# stm32f4x7v.net
KiCad netlist of a schematic drawn in Altium Designer
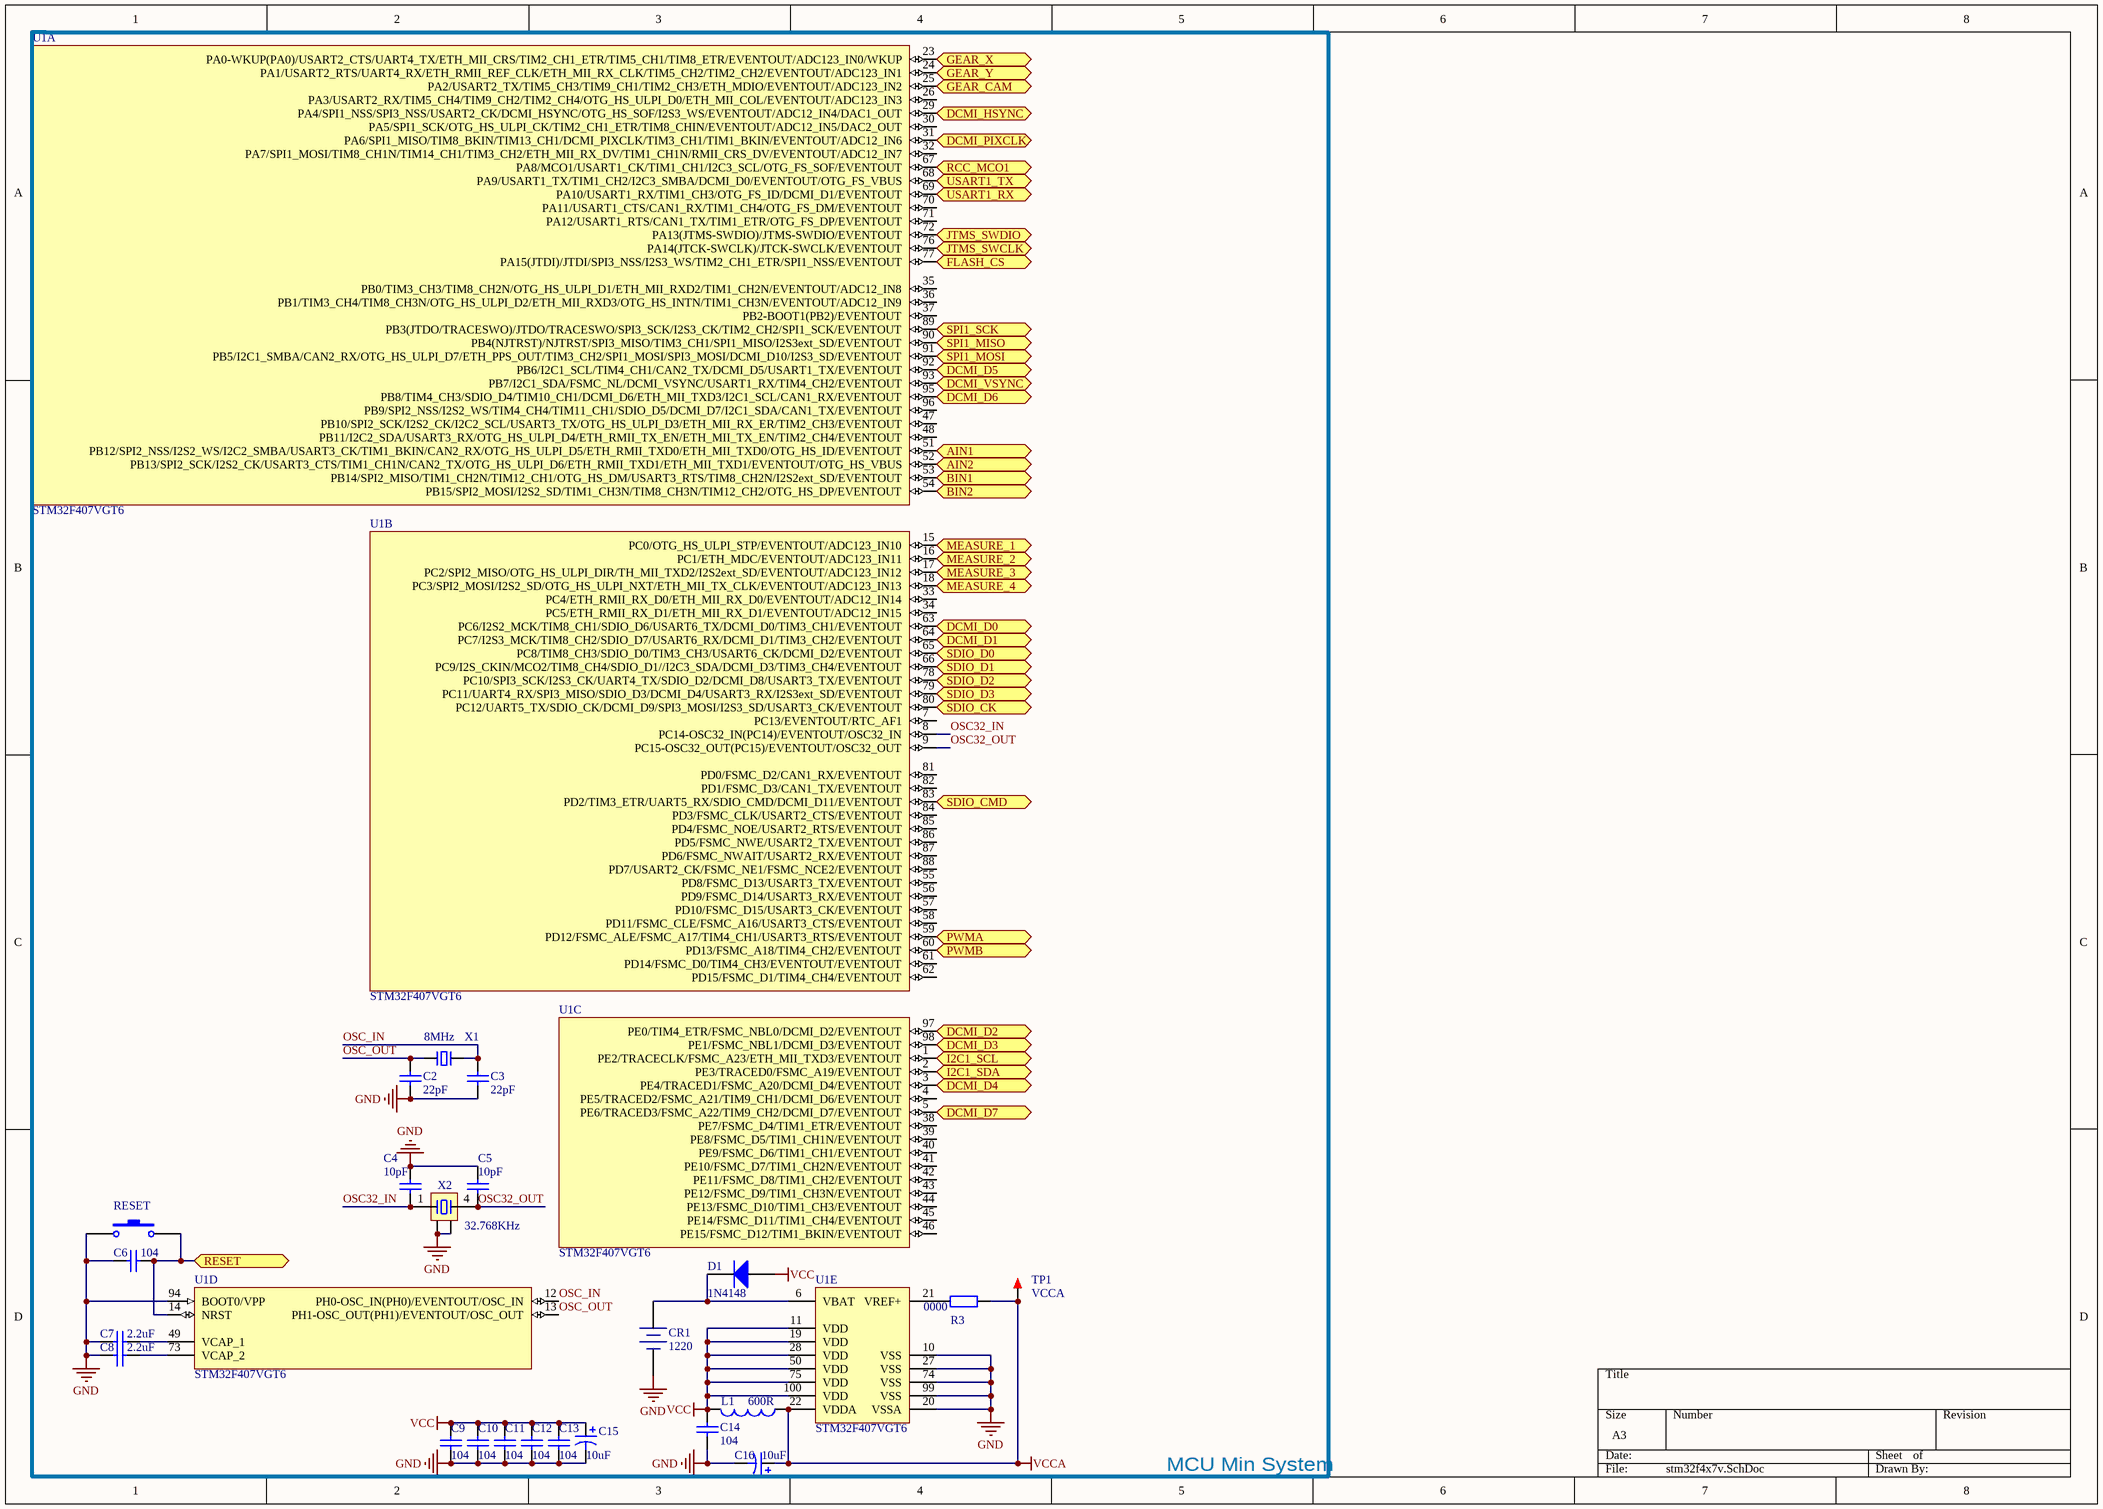
[diagram p0: stm32f4x7v.SchDoc]

(export (version "E")
  (design (tool "Eeschema 10.0.6"))
  (components
    (comp (ref "C2")
      (value "22pF")
      (footprint "C 0603_L")
      (description "Capacitor")
      (fields (field (name "PUBLISHER") "Altium Limited"))
      (libsource (lib "Miscellaneous Devices") (part "Cap"))
    )
    (comp (ref "C3")
      (value "22pF")
      (footprint "C 0603_L")
      (description "Capacitor")
      (fields (field (name "PUBLISHER") "Altium Limited"))
      (libsource (lib "Miscellaneous Devices") (part "Cap"))
    )
    (comp (ref "C4")
      (value "10pF")
      (footprint "C 0603_L")
      (description "Capacitor")
      (fields (field (name "PUBLISHER") "Altium Limited"))
      (libsource (lib "Miscellaneous Devices") (part "Cap"))
    )
    (comp (ref "C5")
      (value "10pF")
      (footprint "C 0603_L")
      (description "Capacitor")
      (fields (field (name "PUBLISHER") "Altium Limited"))
      (libsource (lib "Miscellaneous Devices") (part "Cap"))
    )
    (comp (ref "C6")
      (value "104")
      (footprint "C 0603_L")
      (description "Capacitor")
      (fields (field (name "PUBLISHER") "Altium Limited"))
      (libsource (lib "Miscellaneous Devices") (part "Cap"))
    )
    (comp (ref "C7")
      (value "2.2uF")
      (footprint "C 0603_L")
      (description "Capacitor")
      (fields (field (name "PUBLISHER") "Altium Limited"))
      (libsource (lib "Miscellaneous Devices") (part "Cap"))
    )
    (comp (ref "C8")
      (value "2.2uF")
      (footprint "C 0603_L")
      (description "Capacitor")
      (fields (field (name "PUBLISHER") "Altium Limited"))
      (libsource (lib "Miscellaneous Devices") (part "Cap"))
    )
    (comp (ref "C9")
      (value "104")
      (footprint "C 0603_L")
      (description "Capacitor")
      (fields (field (name "PUBLISHER") "Altium Limited"))
      (libsource (lib "Miscellaneous Devices") (part "Cap"))
    )
    (comp (ref "C10")
      (value "104")
      (footprint "C 0603_L")
      (description "Capacitor")
      (fields (field (name "PUBLISHER") "Altium Limited"))
      (libsource (lib "Miscellaneous Devices") (part "Cap"))
    )
    (comp (ref "C11")
      (value "104")
      (footprint "C 0603_L")
      (description "Capacitor")
      (fields (field (name "PUBLISHER") "Altium Limited"))
      (libsource (lib "Miscellaneous Devices") (part "Cap"))
    )
    (comp (ref "C12")
      (value "104")
      (footprint "C 0603_L")
      (description "Capacitor")
      (fields (field (name "PUBLISHER") "Altium Limited"))
      (libsource (lib "Miscellaneous Devices") (part "Cap"))
    )
    (comp (ref "C13")
      (value "104")
      (footprint "C 0603_L")
      (description "Capacitor")
      (fields (field (name "PUBLISHER") "Altium Limited"))
      (libsource (lib "Miscellaneous Devices") (part "Cap"))
    )
    (comp (ref "C14")
      (value "104")
      (footprint "C 0603_L")
      (description "Capacitor")
      (fields (field (name "PUBLISHER") "Altium Limited"))
      (libsource (lib "Miscellaneous Devices") (part "Cap"))
    )
    (comp (ref "C15")
      (value "10uF")
      (footprint "CD A(3216)")
      (description "Polarized Capacitor (Radial)")
      (fields (field (name "PUBLISHER") "Altium Limited"))
      (libsource (lib "Miscellaneous Devices") (part "Cap Pol1"))
    )
    (comp (ref "C16")
      (value "10uF")
      (footprint "CD A(3216)")
      (description "Polarized Capacitor (Radial)")
      (fields (field (name "PUBLISHER") "Altium Limited"))
      (libsource (lib "Miscellaneous Devices") (part "Cap Pol1"))
    )
    (comp (ref "CR1")
      (value "1220")
      (footprint "ML621FE")
      (description "微型电池")
      (fields (field (name "版权归属") "源创客"))
      (libsource (lib "15.1 - 未分类器件") (part "CR-3V"))
    )
    (comp (ref "D1")
      (value "1N4148")
      (footprint "SOD-523")
      (description "High Conductance Fast Diode")
      (fields (field (name "PUBLISHER") "Altium Limited"))
      (libsource (lib "Miscellaneous Devices") (part "Diode 1N4148"))
    )
    (comp (ref "L1")
      (value "600R")
      (footprint "R 0603_L")
      (description "Inductor")
      (fields (field (name "PUBLISHER") "Altium Limited"))
      (libsource (lib "Miscellaneous Devices") (part "Inductor"))
    )
    (comp (ref "R3")
      (value "0000")
      (footprint "R 0603_L")
      (description "Resistor")
      (fields (field (name "PUBLISHER") "Altium Limited"))
      (libsource (lib "Miscellaneous Devices") (part "Res2"))
    )
    (comp (ref "RESET")
      (value "RESET")
      (footprint "micro button_2_SMD")
      (description "Switch")
      (fields (field (name "PUBLISHER") "Altium Limited"))
      (libsource (lib "Miscellaneous Devices") (part "SW-PB"))
    )
    (comp (ref "TP1")
      (value "VCCA")
      (footprint "TEST 0.8")
      (description "测试点")
      (fields (field (name "版权归属") "源创客"))
      (libsource (lib "15.1 - 未分类器件") (part "TEST"))
    )
    (comp (ref "U1")
      (value "STM32F407VGT6")
      (footprint "LQFP100 14x14_N")
      (libsource (lib "STMicroelectronics STM32 F4") (part "STM32F407VGT6"))
    )
    (comp (ref "X1")
      (value "8MHz")
      (footprint "OSC 5032-2P")
      (description "2脚无源脚晶振")
      (fields (field (name "版权归属") "源创客"))
      (libsource (lib "10.1 - 保险丝-晶振") (part "XTAL-2P"))
    )
    (comp (ref "X2")
      (value "32.768KHz")
      (footprint "OSC MC-146")
      (description "MC系列4脚晶振")
      (fields (field (name "版权归属") "源创客"))
      (libsource (lib "10.1 - 保险丝-晶振") (part "XTAL-MC-4P"))
    )
  )
  (nets
    (net (code "1") (name "/AIN1") (class "Default")
      (node (ref "U1") (pin "51") (pinfunction "PB12/SPI2_NSS/I2S2_WS/I2C2_SMBA/USART3_CK/TIM1_BKIN/CAN2_RX/OTG_HS_ULPI_D5/ETH_RMII_TXD0/ETH_MII_TXD0/OTG_HS_ID/EVENTOUT_51") (pintype "bidirectional"))
    )
    (net (code "2") (name "/AIN2") (class "Default")
      (node (ref "U1") (pin "52") (pinfunction "PB13/SPI2_SCK/I2S2_CK/USART3_CTS/TIM1_CH1N/CAN2_TX/OTG_HS_ULPI_D6/ETH_RMII_TXD1/ETH_MII_TXD1/EVENTOUT/OTG_HS_VBUS_52") (pintype "bidirectional"))
    )
    (net (code "3") (name "/BIN1") (class "Default")
      (node (ref "U1") (pin "53") (pinfunction "PB14/SPI2_MISO/TIM1_CH2N/TIM12_CH1/OTG_HS_DM/USART3_RTS/TIM8_CH2N/I2S2ext_SD/EVENTOUT_53") (pintype "bidirectional"))
    )
    (net (code "4") (name "/BIN2") (class "Default")
      (node (ref "U1") (pin "54") (pinfunction "PB15/SPI2_MOSI/I2S2_SD/TIM1_CH3N/TIM8_CH3N/TIM12_CH2/OTG_HS_DP/EVENTOUT_54") (pintype "bidirectional"))
    )
    (net (code "5") (name "/DCMI_D0") (class "Default")
      (node (ref "U1") (pin "63") (pinfunction "PC6/I2S2_MCK/TIM8_CH1/SDIO_D6/USART6_TX/DCMI_D0/TIM3_CH1/EVENTOUT_63") (pintype "bidirectional"))
    )
    (net (code "6") (name "/DCMI_D1") (class "Default")
      (node (ref "U1") (pin "64") (pinfunction "PC7/I2S3_MCK/TIM8_CH2/SDIO_D7/USART6_RX/DCMI_D1/TIM3_CH2/EVENTOUT_64") (pintype "bidirectional"))
    )
    (net (code "7") (name "/DCMI_D2") (class "Default")
      (node (ref "U1") (pin "97") (pinfunction "PE0/TIM4_ETR/FSMC_NBL0/DCMI_D2/EVENTOUT_97") (pintype "bidirectional"))
    )
    (net (code "8") (name "/DCMI_D3") (class "Default")
      (node (ref "U1") (pin "98") (pinfunction "PE1/FSMC_NBL1/DCMI_D3/EVENTOUT_98") (pintype "bidirectional"))
    )
    (net (code "9") (name "/DCMI_D4") (class "Default")
      (node (ref "U1") (pin "3") (pinfunction "PE4/TRACED1/FSMC_A20/DCMI_D4/EVENTOUT_3") (pintype "bidirectional"))
    )
    (net (code "10") (name "/DCMI_D5") (class "Default")
      (node (ref "U1") (pin "92") (pinfunction "PB6/I2C1_SCL/TIM4_CH1/CAN2_TX/DCMI_D5/USART1_TX/EVENTOUT_92") (pintype "bidirectional"))
    )
    (net (code "11") (name "/DCMI_D6") (class "Default")
      (node (ref "U1") (pin "95") (pinfunction "PB8/TIM4_CH3/SDIO_D4/TIM10_CH1/DCMI_D6/ETH_MII_TXD3/I2C1_SCL/CAN1_RX/EVENTOUT_95") (pintype "bidirectional"))
    )
    (net (code "12") (name "/DCMI_D7") (class "Default")
      (node (ref "U1") (pin "5") (pinfunction "PE6/TRACED3/FSMC_A22/TIM9_CH2/DCMI_D7/EVENTOUT_5") (pintype "bidirectional"))
    )
    (net (code "13") (name "/DCMI_HSYNC") (class "Default")
      (node (ref "U1") (pin "29") (pinfunction "PA4/SPI1_NSS/SPI3_NSS/USART2_CK/DCMI_HSYNC/OTG_HS_SOF/I2S3_WS/EVENTOUT/ADC12_IN4/DAC1_OUT_29") (pintype "bidirectional"))
    )
    (net (code "14") (name "/DCMI_PIXCLK") (class "Default")
      (node (ref "U1") (pin "31") (pinfunction "PA6/SPI1_MISO/TIM8_BKIN/TIM13_CH1/DCMI_PIXCLK/TIM3_CH1/TIM1_BKIN/EVENTOUT/ADC12_IN6_31") (pintype "bidirectional"))
    )
    (net (code "15") (name "/DCMI_VSYNC") (class "Default")
      (node (ref "U1") (pin "93") (pinfunction "PB7/I2C1_SDA/FSMC_NL/DCMI_VSYNC/USART1_RX/TIM4_CH2/EVENTOUT_93") (pintype "bidirectional"))
    )
    (net (code "16") (name "/FLASH_CS") (class "Default")
      (node (ref "U1") (pin "77") (pinfunction "PA15(JTDI)/JTDI/SPI3_NSS/I2S3_WS/TIM2_CH1_ETR/SPI1_NSS/EVENTOUT_77") (pintype "bidirectional"))
    )
    (net (code "17") (name "/GEAR_CAM") (class "Default")
      (node (ref "U1") (pin "25") (pinfunction "PA2/USART2_TX/TIM5_CH3/TIM9_CH1/TIM2_CH3/ETH_MDIO/EVENTOUT/ADC123_IN2_25") (pintype "bidirectional"))
    )
    (net (code "18") (name "/GEAR_X") (class "Default")
      (node (ref "U1") (pin "23") (pinfunction "PA0-WKUP(PA0)/USART2_CTS/UART4_TX/ETH_MII_CRS/TIM2_CH1_ETR/TIM5_CH1/TIM8_ETR/EVENTOUT/ADC123_IN0/WKUP_23") (pintype "bidirectional"))
    )
    (net (code "19") (name "/GEAR_Y") (class "Default")
      (node (ref "U1") (pin "24") (pinfunction "PA1/USART2_RTS/UART4_RX/ETH_RMII_REF_CLK/ETH_MII_RX_CLK/TIM5_CH2/TIM2_CH2/EVENTOUT/ADC123_IN1_24") (pintype "bidirectional"))
    )
    (net (code "20") (name "/I2C1_SCL") (class "Default")
      (node (ref "U1") (pin "1") (pinfunction "PE2/TRACECLK/FSMC_A23/ETH_MII_TXD3/EVENTOUT_1") (pintype "bidirectional"))
    )
    (net (code "21") (name "/I2C1_SDA") (class "Default")
      (node (ref "U1") (pin "2") (pinfunction "PE3/TRACED0/FSMC_A19/EVENTOUT_2") (pintype "bidirectional"))
    )
    (net (code "22") (name "/JTMS_SWCLK") (class "Default")
      (node (ref "U1") (pin "76") (pinfunction "PA14(JTCK-SWCLK)/JTCK-SWCLK/EVENTOUT_76") (pintype "bidirectional"))
    )
    (net (code "23") (name "/JTMS_SWDIO") (class "Default")
      (node (ref "U1") (pin "72") (pinfunction "PA13(JTMS-SWDIO)/JTMS-SWDIO/EVENTOUT_72") (pintype "bidirectional"))
    )
    (net (code "24") (name "/MEASURE_1") (class "Default")
      (node (ref "U1") (pin "15") (pinfunction "PC0/OTG_HS_ULPI_STP/EVENTOUT/ADC123_IN10_15") (pintype "bidirectional"))
    )
    (net (code "25") (name "/MEASURE_2") (class "Default")
      (node (ref "U1") (pin "16") (pinfunction "PC1/ETH_MDC/EVENTOUT/ADC123_IN11_16") (pintype "bidirectional"))
    )
    (net (code "26") (name "/MEASURE_3") (class "Default")
      (node (ref "U1") (pin "17") (pinfunction "PC2/SPI2_MISO/OTG_HS_ULPI_DIR/TH_MII_TXD2/I2S2ext_SD/EVENTOUT/ADC123_IN12_17") (pintype "bidirectional"))
    )
    (net (code "27") (name "/MEASURE_4") (class "Default")
      (node (ref "U1") (pin "18") (pinfunction "PC3/SPI2_MOSI/I2S2_SD/OTG_HS_ULPI_NXT/ETH_MII_TX_CLK/EVENTOUT/ADC123_IN13_18") (pintype "bidirectional"))
    )
    (net (code "28") (name "/OSC32_IN") (class "Default")
      (node (ref "C4") (pin "1") (pinfunction "1_1") (pintype "passive"))
      (node (ref "U1") (pin "8") (pinfunction "PC14-OSC32_IN(PC14)/EVENTOUT/OSC32_IN_8") (pintype "bidirectional"))
      (node (ref "X2") (pin "1") (pinfunction "1_1") (pintype "passive"))
    )
    (net (code "29") (name "/OSC32_OUT") (class "Default")
      (node (ref "C5") (pin "1") (pinfunction "1_1") (pintype "passive"))
      (node (ref "U1") (pin "9") (pinfunction "PC15-OSC32_OUT(PC15)/EVENTOUT/OSC32_OUT_9") (pintype "bidirectional"))
      (node (ref "X2") (pin "4") (pinfunction "4_4") (pintype "passive"))
    )
    (net (code "30") (name "/OSC_IN") (class "Default")
      (node (ref "C3") (pin "2") (pinfunction "2_2") (pintype "passive"))
      (node (ref "U1") (pin "12") (pinfunction "PH0-OSC_IN(PH0)/EVENTOUT/OSC_IN_12") (pintype "bidirectional"))
      (node (ref "X1") (pin "2") (pinfunction "2_2") (pintype "passive"))
    )
    (net (code "31") (name "/OSC_OUT") (class "Default")
      (node (ref "C2") (pin "2") (pinfunction "2_2") (pintype "passive"))
      (node (ref "U1") (pin "13") (pinfunction "PH1-OSC_OUT(PH1)/EVENTOUT/OSC_OUT_13") (pintype "bidirectional"))
      (node (ref "X1") (pin "1") (pinfunction "1_1") (pintype "passive"))
    )
    (net (code "32") (name "/PWMA") (class "Default")
      (node (ref "U1") (pin "59") (pinfunction "PD12/FSMC_ALE/FSMC_A17/TIM4_CH1/USART3_RTS/EVENTOUT_59") (pintype "bidirectional"))
    )
    (net (code "33") (name "/PWMB") (class "Default")
      (node (ref "U1") (pin "60") (pinfunction "PD13/FSMC_A18/TIM4_CH2/EVENTOUT_60") (pintype "bidirectional"))
    )
    (net (code "34") (name "/RCC_MCO1") (class "Default")
      (node (ref "U1") (pin "67") (pinfunction "PA8/MCO1/USART1_CK/TIM1_CH1/I2C3_SCL/OTG_FS_SOF/EVENTOUT_67") (pintype "bidirectional"))
    )
    (net (code "35") (name "/RESET") (class "Default")
      (node (ref "C6") (pin "2") (pinfunction "2_2") (pintype "passive"))
      (node (ref "RESET") (pin "2") (pinfunction "2_2") (pintype "passive"))
      (node (ref "U1") (pin "14") (pinfunction "NRST_14") (pintype "bidirectional"))
    )
    (net (code "36") (name "/SDIO_CK") (class "Default")
      (node (ref "U1") (pin "80") (pinfunction "PC12/UART5_TX/SDIO_CK/DCMI_D9/SPI3_MOSI/I2S3_SD/USART3_CK/EVENTOUT_80") (pintype "bidirectional"))
    )
    (net (code "37") (name "/SDIO_CMD") (class "Default")
      (node (ref "U1") (pin "83") (pinfunction "PD2/TIM3_ETR/UART5_RX/SDIO_CMD/DCMI_D11/EVENTOUT_83") (pintype "bidirectional"))
    )
    (net (code "38") (name "/SDIO_D0") (class "Default")
      (node (ref "U1") (pin "65") (pinfunction "PC8/TIM8_CH3/SDIO_D0/TIM3_CH3/USART6_CK/DCMI_D2/EVENTOUT_65") (pintype "bidirectional"))
    )
    (net (code "39") (name "/SDIO_D1") (class "Default")
      (node (ref "U1") (pin "66") (pinfunction "PC9/I2S_CKIN/MCO2/TIM8_CH4/SDIO_D1//I2C3_SDA/DCMI_D3/TIM3_CH4/EVENTOUT_66") (pintype "bidirectional"))
    )
    (net (code "40") (name "/SDIO_D2") (class "Default")
      (node (ref "U1") (pin "78") (pinfunction "PC10/SPI3_SCK/I2S3_CK/UART4_TX/SDIO_D2/DCMI_D8/USART3_TX/EVENTOUT_78") (pintype "bidirectional"))
    )
    (net (code "41") (name "/SDIO_D3") (class "Default")
      (node (ref "U1") (pin "79") (pinfunction "PC11/UART4_RX/SPI3_MISO/SDIO_D3/DCMI_D4/USART3_RX/I2S3ext_SD/EVENTOUT_79") (pintype "bidirectional"))
    )
    (net (code "42") (name "/SPI1_MISO") (class "Default")
      (node (ref "U1") (pin "90") (pinfunction "PB4(NJTRST)/NJTRST/SPI3_MISO/TIM3_CH1/SPI1_MISO/I2S3ext_SD/EVENTOUT_90") (pintype "bidirectional"))
    )
    (net (code "43") (name "/SPI1_MOSI") (class "Default")
      (node (ref "U1") (pin "91") (pinfunction "PB5/I2C1_SMBA/CAN2_RX/OTG_HS_ULPI_D7/ETH_PPS_OUT/TIM3_CH2/SPI1_MOSI/SPI3_MOSI/DCMI_D10/I2S3_SD/EVENTOUT_91") (pintype "bidirectional"))
    )
    (net (code "44") (name "/SPI1_SCK") (class "Default")
      (node (ref "U1") (pin "89") (pinfunction "PB3(JTDO/TRACESWO)/JTDO/TRACESWO/SPI3_SCK/I2S3_CK/TIM2_CH2/SPI1_SCK/EVENTOUT_89") (pintype "bidirectional"))
    )
    (net (code "45") (name "/USART1_RX") (class "Default")
      (node (ref "U1") (pin "69") (pinfunction "PA10/USART1_RX/TIM1_CH3/OTG_FS_ID/DCMI_D1/EVENTOUT_69") (pintype "bidirectional"))
    )
    (net (code "46") (name "/USART1_TX") (class "Default")
      (node (ref "U1") (pin "68") (pinfunction "PA9/USART1_TX/TIM1_CH2/I2C3_SMBA/DCMI_D0/EVENTOUT/OTG_FS_VBUS_68") (pintype "bidirectional"))
    )
    (net (code "47") (name "GND") (class "Default")
      (node (ref "C10") (pin "1") (pinfunction "1_1") (pintype "passive"))
      (node (ref "C11") (pin "1") (pinfunction "1_1") (pintype "passive"))
      (node (ref "C12") (pin "1") (pinfunction "1_1") (pintype "passive"))
      (node (ref "C13") (pin "1") (pinfunction "1_1") (pintype "passive"))
      (node (ref "C14") (pin "1") (pinfunction "1_1") (pintype "passive"))
      (node (ref "C15") (pin "2") (pinfunction "2_2") (pintype "passive"))
      (node (ref "C16") (pin "2") (pinfunction "2_2") (pintype "passive"))
      (node (ref "C2") (pin "1") (pinfunction "1_1") (pintype "passive"))
      (node (ref "C3") (pin "1") (pinfunction "1_1") (pintype "passive"))
      (node (ref "C4") (pin "2") (pinfunction "2_2") (pintype "passive"))
      (node (ref "C5") (pin "2") (pinfunction "2_2") (pintype "passive"))
      (node (ref "C6") (pin "1") (pinfunction "1_1") (pintype "passive"))
      (node (ref "C7") (pin "1") (pinfunction "1_1") (pintype "passive"))
      (node (ref "C8") (pin "1") (pinfunction "1_1") (pintype "passive"))
      (node (ref "C9") (pin "1") (pinfunction "1_1") (pintype "passive"))
      (node (ref "CR1") (pin "2") (pinfunction "DC-_2") (pintype "passive"))
      (node (ref "RESET") (pin "1") (pinfunction "1_1") (pintype "passive"))
      (node (ref "U1") (pin "10") (pinfunction "VSS_10") (pintype "power_in"))
      (node (ref "U1") (pin "20") (pinfunction "VSSA_20") (pintype "power_in"))
      (node (ref "U1") (pin "27") (pinfunction "VSS_27") (pintype "power_in"))
      (node (ref "U1") (pin "74") (pinfunction "VSS_74") (pintype "power_in"))
      (node (ref "U1") (pin "94") (pinfunction "BOOT0/VPP_94") (pintype "input"))
      (node (ref "U1") (pin "99") (pinfunction "VSS_99") (pintype "power_in"))
      (node (ref "X2") (pin "2") (pinfunction "2_2") (pintype "passive"))
      (node (ref "X2") (pin "3") (pinfunction "3_3") (pintype "passive"))
    )
    (net (code "48") (name "Net-(CR1-DC+)") (class "Default")
      (node (ref "CR1") (pin "1") (pinfunction "DC+_1") (pintype "passive"))
      (node (ref "D1") (pin "2") (pinfunction "K_2") (pintype "passive"))
      (node (ref "U1") (pin "6") (pinfunction "VBAT_6") (pintype "power_in"))
    )
    (net (code "49") (name "Net-(U1D-VCAP_1)") (class "Default")
      (node (ref "C7") (pin "2") (pinfunction "2_2") (pintype "passive"))
      (node (ref "U1") (pin "49") (pinfunction "VCAP_1_49") (pintype "power_in"))
    )
    (net (code "50") (name "Net-(U1D-VCAP_2)") (class "Default")
      (node (ref "C8") (pin "2") (pinfunction "2_2") (pintype "passive"))
      (node (ref "U1") (pin "73") (pinfunction "VCAP_2_73") (pintype "power_in"))
    )
    (net (code "51") (name "Net-(U1E-VREF+)") (class "Default")
      (node (ref "R3") (pin "2") (pinfunction "2_2") (pintype "passive"))
      (node (ref "U1") (pin "21") (pinfunction "VREF+_21") (pintype "power_in"))
    )
    (net (code "52") (name "VCC") (class "Default")
      (node (ref "C10") (pin "2") (pinfunction "2_2") (pintype "passive"))
      (node (ref "C11") (pin "2") (pinfunction "2_2") (pintype "passive"))
      (node (ref "C12") (pin "2") (pinfunction "2_2") (pintype "passive"))
      (node (ref "C13") (pin "2") (pinfunction "2_2") (pintype "passive"))
      (node (ref "C14") (pin "2") (pinfunction "2_2") (pintype "passive"))
      (node (ref "C15") (pin "1") (pinfunction "1_1") (pintype "passive"))
      (node (ref "C9") (pin "2") (pinfunction "2_2") (pintype "passive"))
      (node (ref "D1") (pin "1") (pinfunction "A_1") (pintype "passive"))
      (node (ref "L1") (pin "2") (pinfunction "2_2") (pintype "passive"))
      (node (ref "U1") (pin "100") (pinfunction "VDD_100") (pintype "power_in"))
      (node (ref "U1") (pin "11") (pinfunction "VDD_11") (pintype "power_in"))
      (node (ref "U1") (pin "19") (pinfunction "VDD_19") (pintype "power_in"))
      (node (ref "U1") (pin "28") (pinfunction "VDD_28") (pintype "power_in"))
      (node (ref "U1") (pin "50") (pinfunction "VDD_50") (pintype "power_in"))
      (node (ref "U1") (pin "75") (pinfunction "VDD_75") (pintype "power_in"))
    )
    (net (code "53") (name "VCCA") (class "Default")
      (node (ref "C16") (pin "1") (pinfunction "1_1") (pintype "passive"))
      (node (ref "L1") (pin "1") (pinfunction "1_1") (pintype "passive"))
      (node (ref "R3") (pin "1") (pinfunction "1_1") (pintype "passive"))
      (node (ref "TP1") (pin "1") (pinfunction "1_1") (pintype "passive"))
      (node (ref "U1") (pin "22") (pinfunction "VDDA_22") (pintype "power_in"))
    )
    (net (code "54") (name "unconnected-(U1A-PA3{slash}USART2_RX{slash}TIM5_CH4{slash}TIM9_CH2{slash}TIM2_CH4{slash}OTG_HS_ULPI_D0{slash}ETH_MII_COL{slash}EVENTOUT{slash}ADC123_IN3-Pad26)") (class "Default")
      (node (ref "U1") (pin "26") (pinfunction "PA3/USART2_RX/TIM5_CH4/TIM9_CH2/TIM2_CH4/OTG_HS_ULPI_D0/ETH_MII_COL/EVENTOUT/ADC123_IN3_26") (pintype "bidirectional"))
    )
    (net (code "55") (name "unconnected-(U1A-PA5{slash}SPI1_SCK{slash}OTG_HS_ULPI_CK{slash}TIM2_CH1_ETR{slash}TIM8_CHIN{slash}EVENTOUT{slash}ADC12_IN5{slash}DAC2_OUT-Pad30)") (class "Default")
      (node (ref "U1") (pin "30") (pinfunction "PA5/SPI1_SCK/OTG_HS_ULPI_CK/TIM2_CH1_ETR/TIM8_CHIN/EVENTOUT/ADC12_IN5/DAC2_OUT_30") (pintype "bidirectional"))
    )
    (net (code "56") (name "unconnected-(U1A-PA7{slash}SPI1_MOSI{slash}TIM8_CH1N{slash}TIM14_CH1{slash}TIM3_CH2{slash}ETH_MII_RX_DV{slash}TIM1_CH1N{slash}RMII_CRS_DV{slash}EVENTOUT{slash}ADC12_IN7-Pad32)") (class "Default")
      (node (ref "U1") (pin "32") (pinfunction "PA7/SPI1_MOSI/TIM8_CH1N/TIM14_CH1/TIM3_CH2/ETH_MII_RX_DV/TIM1_CH1N/RMII_CRS_DV/EVENTOUT/ADC12_IN7_32") (pintype "bidirectional"))
    )
    (net (code "57") (name "unconnected-(U1A-PA11{slash}USART1_CTS{slash}CAN1_RX{slash}TIM1_CH4{slash}OTG_FS_DM{slash}EVENTOUT-Pad70)") (class "Default")
      (node (ref "U1") (pin "70") (pinfunction "PA11/USART1_CTS/CAN1_RX/TIM1_CH4/OTG_FS_DM/EVENTOUT_70") (pintype "bidirectional"))
    )
    (net (code "58") (name "unconnected-(U1A-PA12{slash}USART1_RTS{slash}CAN1_TX{slash}TIM1_ETR{slash}OTG_FS_DP{slash}EVENTOUT-Pad71)") (class "Default")
      (node (ref "U1") (pin "71") (pinfunction "PA12/USART1_RTS/CAN1_TX/TIM1_ETR/OTG_FS_DP/EVENTOUT_71") (pintype "bidirectional"))
    )
    (net (code "59") (name "unconnected-(U1A-PB0{slash}TIM3_CH3{slash}TIM8_CH2N{slash}OTG_HS_ULPI_D1{slash}ETH_MII_RXD2{slash}TIM1_CH2N{slash}EVENTOUT{slash}ADC12_IN8-Pad35)") (class "Default")
      (node (ref "U1") (pin "35") (pinfunction "PB0/TIM3_CH3/TIM8_CH2N/OTG_HS_ULPI_D1/ETH_MII_RXD2/TIM1_CH2N/EVENTOUT/ADC12_IN8_35") (pintype "bidirectional"))
    )
    (net (code "60") (name "unconnected-(U1A-PB1{slash}TIM3_CH4{slash}TIM8_CH3N{slash}OTG_HS_ULPI_D2{slash}ETH_MII_RXD3{slash}OTG_HS_INTN{slash}TIM1_CH3N{slash}EVENTOUT{slash}ADC12_IN9-Pad36)") (class "Default")
      (node (ref "U1") (pin "36") (pinfunction "PB1/TIM3_CH4/TIM8_CH3N/OTG_HS_ULPI_D2/ETH_MII_RXD3/OTG_HS_INTN/TIM1_CH3N/EVENTOUT/ADC12_IN9_36") (pintype "bidirectional"))
    )
    (net (code "61") (name "unconnected-(U1A-PB2-BOOT1(PB2){slash}EVENTOUT-Pad37)") (class "Default")
      (node (ref "U1") (pin "37") (pinfunction "PB2-BOOT1(PB2)/EVENTOUT_37") (pintype "bidirectional"))
    )
    (net (code "62") (name "unconnected-(U1A-PB9{slash}SPI2_NSS{slash}I2S2_WS{slash}TIM4_CH4{slash}TIM11_CH1{slash}SDIO_D5{slash}DCMI_D7{slash}I2C1_SDA{slash}CAN1_TX{slash}EVENTOUT-Pad96)") (class "Default")
      (node (ref "U1") (pin "96") (pinfunction "PB9/SPI2_NSS/I2S2_WS/TIM4_CH4/TIM11_CH1/SDIO_D5/DCMI_D7/I2C1_SDA/CAN1_TX/EVENTOUT_96") (pintype "bidirectional"))
    )
    (net (code "63") (name "unconnected-(U1A-PB10{slash}SPI2_SCK{slash}I2S2_CK{slash}I2C2_SCL{slash}USART3_TX{slash}OTG_HS_ULPI_D3{slash}ETH_MII_RX_ER{slash}TIM2_CH3{slash}EVENTOUT-Pad47)") (class "Default")
      (node (ref "U1") (pin "47") (pinfunction "PB10/SPI2_SCK/I2S2_CK/I2C2_SCL/USART3_TX/OTG_HS_ULPI_D3/ETH_MII_RX_ER/TIM2_CH3/EVENTOUT_47") (pintype "bidirectional"))
    )
    (net (code "64") (name "unconnected-(U1A-PB11{slash}I2C2_SDA{slash}USART3_RX{slash}OTG_HS_ULPI_D4{slash}ETH_RMII_TX_EN{slash}ETH_MII_TX_EN{slash}TIM2_CH4{slash}EVENTOUT-Pad48)") (class "Default")
      (node (ref "U1") (pin "48") (pinfunction "PB11/I2C2_SDA/USART3_RX/OTG_HS_ULPI_D4/ETH_RMII_TX_EN/ETH_MII_TX_EN/TIM2_CH4/EVENTOUT_48") (pintype "bidirectional"))
    )
    (net (code "65") (name "unconnected-(U1B-PC4{slash}ETH_RMII_RX_D0{slash}ETH_MII_RX_D0{slash}EVENTOUT{slash}ADC12_IN14-Pad33)") (class "Default")
      (node (ref "U1") (pin "33") (pinfunction "PC4/ETH_RMII_RX_D0/ETH_MII_RX_D0/EVENTOUT/ADC12_IN14_33") (pintype "bidirectional"))
    )
    (net (code "66") (name "unconnected-(U1B-PC5{slash}ETH_RMII_RX_D1{slash}ETH_MII_RX_D1{slash}EVENTOUT{slash}ADC12_IN15-Pad34)") (class "Default")
      (node (ref "U1") (pin "34") (pinfunction "PC5/ETH_RMII_RX_D1/ETH_MII_RX_D1/EVENTOUT/ADC12_IN15_34") (pintype "bidirectional"))
    )
    (net (code "67") (name "unconnected-(U1B-PC13{slash}EVENTOUT{slash}RTC_AF1-Pad7)") (class "Default")
      (node (ref "U1") (pin "7") (pinfunction "PC13/EVENTOUT/RTC_AF1_7") (pintype "bidirectional"))
    )
    (net (code "68") (name "unconnected-(U1B-PD0{slash}FSMC_D2{slash}CAN1_RX{slash}EVENTOUT-Pad81)") (class "Default")
      (node (ref "U1") (pin "81") (pinfunction "PD0/FSMC_D2/CAN1_RX/EVENTOUT_81") (pintype "bidirectional"))
    )
    (net (code "69") (name "unconnected-(U1B-PD1{slash}FSMC_D3{slash}CAN1_TX{slash}EVENTOUT-Pad82)") (class "Default")
      (node (ref "U1") (pin "82") (pinfunction "PD1/FSMC_D3/CAN1_TX/EVENTOUT_82") (pintype "bidirectional"))
    )
    (net (code "70") (name "unconnected-(U1B-PD3{slash}FSMC_CLK{slash}USART2_CTS{slash}EVENTOUT-Pad84)") (class "Default")
      (node (ref "U1") (pin "84") (pinfunction "PD3/FSMC_CLK/USART2_CTS/EVENTOUT_84") (pintype "bidirectional"))
    )
    (net (code "71") (name "unconnected-(U1B-PD4{slash}FSMC_NOE{slash}USART2_RTS{slash}EVENTOUT-Pad85)") (class "Default")
      (node (ref "U1") (pin "85") (pinfunction "PD4/FSMC_NOE/USART2_RTS/EVENTOUT_85") (pintype "bidirectional"))
    )
    (net (code "72") (name "unconnected-(U1B-PD5{slash}FSMC_NWE{slash}USART2_TX{slash}EVENTOUT-Pad86)") (class "Default")
      (node (ref "U1") (pin "86") (pinfunction "PD5/FSMC_NWE/USART2_TX/EVENTOUT_86") (pintype "bidirectional"))
    )
    (net (code "73") (name "unconnected-(U1B-PD6{slash}FSMC_NWAIT{slash}USART2_RX{slash}EVENTOUT-Pad87)") (class "Default")
      (node (ref "U1") (pin "87") (pinfunction "PD6/FSMC_NWAIT/USART2_RX/EVENTOUT_87") (pintype "bidirectional"))
    )
    (net (code "74") (name "unconnected-(U1B-PD7{slash}USART2_CK{slash}FSMC_NE1{slash}FSMC_NCE2{slash}EVENTOUT-Pad88)") (class "Default")
      (node (ref "U1") (pin "88") (pinfunction "PD7/USART2_CK/FSMC_NE1/FSMC_NCE2/EVENTOUT_88") (pintype "bidirectional"))
    )
    (net (code "75") (name "unconnected-(U1B-PD8{slash}FSMC_D13{slash}USART3_TX{slash}EVENTOUT-Pad55)") (class "Default")
      (node (ref "U1") (pin "55") (pinfunction "PD8/FSMC_D13/USART3_TX/EVENTOUT_55") (pintype "bidirectional"))
    )
    (net (code "76") (name "unconnected-(U1B-PD9{slash}FSMC_D14{slash}USART3_RX{slash}EVENTOUT-Pad56)") (class "Default")
      (node (ref "U1") (pin "56") (pinfunction "PD9/FSMC_D14/USART3_RX/EVENTOUT_56") (pintype "bidirectional"))
    )
    (net (code "77") (name "unconnected-(U1B-PD10{slash}FSMC_D15{slash}USART3_CK{slash}EVENTOUT-Pad57)") (class "Default")
      (node (ref "U1") (pin "57") (pinfunction "PD10/FSMC_D15/USART3_CK/EVENTOUT_57") (pintype "bidirectional"))
    )
    (net (code "78") (name "unconnected-(U1B-PD11{slash}FSMC_CLE{slash}FSMC_A16{slash}USART3_CTS{slash}EVENTOUT-Pad58)") (class "Default")
      (node (ref "U1") (pin "58") (pinfunction "PD11/FSMC_CLE/FSMC_A16/USART3_CTS/EVENTOUT_58") (pintype "bidirectional"))
    )
    (net (code "79") (name "unconnected-(U1B-PD14{slash}FSMC_D0{slash}TIM4_CH3{slash}EVENTOUT{slash}EVENTOUT-Pad61)") (class "Default")
      (node (ref "U1") (pin "61") (pinfunction "PD14/FSMC_D0/TIM4_CH3/EVENTOUT/EVENTOUT_61") (pintype "bidirectional"))
    )
    (net (code "80") (name "unconnected-(U1B-PD15{slash}FSMC_D1{slash}TIM4_CH4{slash}EVENTOUT-Pad62)") (class "Default")
      (node (ref "U1") (pin "62") (pinfunction "PD15/FSMC_D1/TIM4_CH4/EVENTOUT_62") (pintype "bidirectional"))
    )
    (net (code "81") (name "unconnected-(U1C-PE5{slash}TRACED2{slash}FSMC_A21{slash}TIM9_CH1{slash}DCMI_D6{slash}EVENTOUT-Pad4)") (class "Default")
      (node (ref "U1") (pin "4") (pinfunction "PE5/TRACED2/FSMC_A21/TIM9_CH1/DCMI_D6/EVENTOUT_4") (pintype "bidirectional"))
    )
    (net (code "82") (name "unconnected-(U1C-PE7{slash}FSMC_D4{slash}TIM1_ETR{slash}EVENTOUT-Pad38)") (class "Default")
      (node (ref "U1") (pin "38") (pinfunction "PE7/FSMC_D4/TIM1_ETR/EVENTOUT_38") (pintype "bidirectional"))
    )
    (net (code "83") (name "unconnected-(U1C-PE8{slash}FSMC_D5{slash}TIM1_CH1N{slash}EVENTOUT-Pad39)") (class "Default")
      (node (ref "U1") (pin "39") (pinfunction "PE8/FSMC_D5/TIM1_CH1N/EVENTOUT_39") (pintype "bidirectional"))
    )
    (net (code "84") (name "unconnected-(U1C-PE9{slash}FSMC_D6{slash}TIM1_CH1{slash}EVENTOUT-Pad40)") (class "Default")
      (node (ref "U1") (pin "40") (pinfunction "PE9/FSMC_D6/TIM1_CH1/EVENTOUT_40") (pintype "bidirectional"))
    )
    (net (code "85") (name "unconnected-(U1C-PE10{slash}FSMC_D7{slash}TIM1_CH2N{slash}EVENTOUT-Pad41)") (class "Default")
      (node (ref "U1") (pin "41") (pinfunction "PE10/FSMC_D7/TIM1_CH2N/EVENTOUT_41") (pintype "bidirectional"))
    )
    (net (code "86") (name "unconnected-(U1C-PE11{slash}FSMC_D8{slash}TIM1_CH2{slash}EVENTOUT-Pad42)") (class "Default")
      (node (ref "U1") (pin "42") (pinfunction "PE11/FSMC_D8/TIM1_CH2/EVENTOUT_42") (pintype "bidirectional"))
    )
    (net (code "87") (name "unconnected-(U1C-PE12{slash}FSMC_D9{slash}TIM1_CH3N{slash}EVENTOUT-Pad43)") (class "Default")
      (node (ref "U1") (pin "43") (pinfunction "PE12/FSMC_D9/TIM1_CH3N/EVENTOUT_43") (pintype "bidirectional"))
    )
    (net (code "88") (name "unconnected-(U1C-PE13{slash}FSMC_D10{slash}TIM1_CH3{slash}EVENTOUT-Pad44)") (class "Default")
      (node (ref "U1") (pin "44") (pinfunction "PE13/FSMC_D10/TIM1_CH3/EVENTOUT_44") (pintype "bidirectional"))
    )
    (net (code "89") (name "unconnected-(U1C-PE14{slash}FSMC_D11{slash}TIM1_CH4{slash}EVENTOUT-Pad45)") (class "Default")
      (node (ref "U1") (pin "45") (pinfunction "PE14/FSMC_D11/TIM1_CH4/EVENTOUT_45") (pintype "bidirectional"))
    )
    (net (code "90") (name "unconnected-(U1C-PE15{slash}FSMC_D12{slash}TIM1_BKIN{slash}EVENTOUT-Pad46)") (class "Default")
      (node (ref "U1") (pin "46") (pinfunction "PE15/FSMC_D12/TIM1_BKIN/EVENTOUT_46") (pintype "bidirectional"))
    )
  )
)
